# ExpandBoardZero.net
KiCad netlist of a schematic drawn in Altium Designer
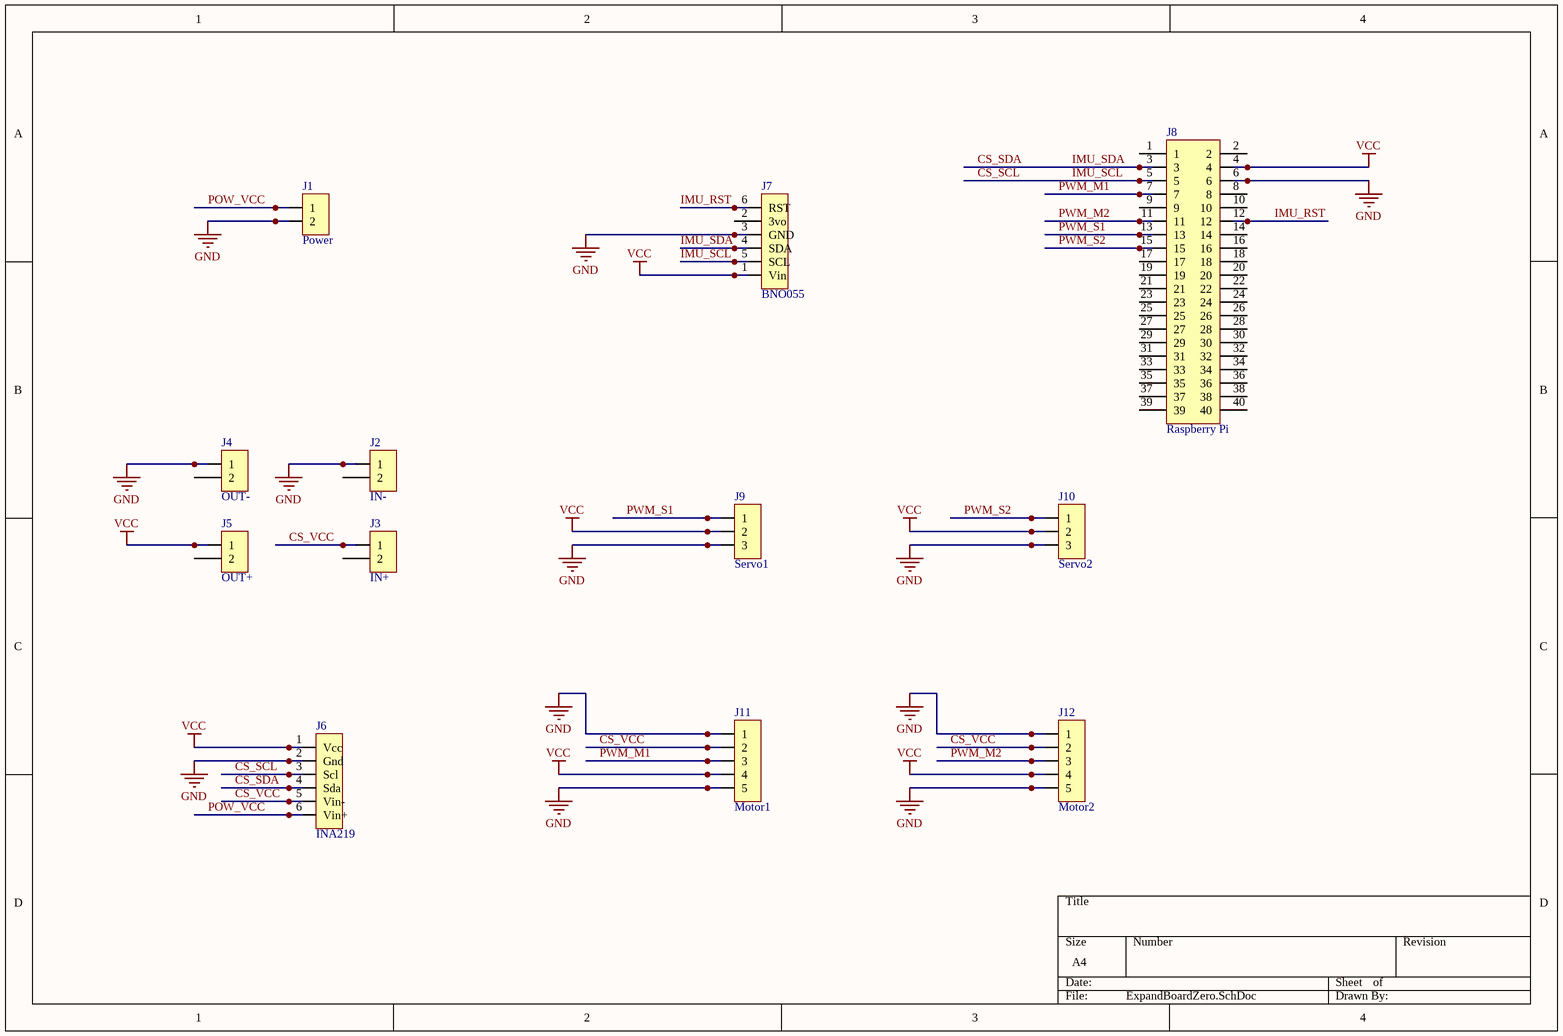
[diagram p0: ExpandBoardZero.SchDoc]

(export (version "E")
  (design (tool "Eeschema 10.0.6"))
  (components
    (comp (ref "J1")
      (value "Power")
      (footprint "Pin HDR1X2/2.54mm-S")
      (libsource (lib "排针") (part "Pin HDR1X2"))
    )
    (comp (ref "J2")
      (value "IN-")
      (footprint "Pin HDR1X2/2.54mm-S")
      (libsource (lib "排针") (part "Pin HDR1X2"))
    )
    (comp (ref "J3")
      (value "IN+")
      (footprint "Pin HDR1X2/2.54mm-S")
      (libsource (lib "排针") (part "Pin HDR1X2"))
    )
    (comp (ref "J4")
      (value "OUT-")
      (footprint "Pin HDR1X2/2.54mm-S")
      (libsource (lib "排针") (part "Pin HDR1X2"))
    )
    (comp (ref "J5")
      (value "OUT+")
      (footprint "Pin HDR1X2/2.54mm-S")
      (libsource (lib "排针") (part "Pin HDR1X2"))
    )
    (comp (ref "J6")
      (value "INA219")
      (footprint "Pin HDR1X6/2.54mm-S")
      (libsource (lib "") (part "Pin HDR1X6_1"))
    )
    (comp (ref "J7")
      (value "BNO055")
      (footprint "Pin HDR1X6/2.54mm-S")
      (libsource (lib "排针") (part "Pin HDR1X6"))
    )
    (comp (ref "J8")
      (value "Raspberry Pi")
      (footprint "Pin HDR2X20/2.54mm-S")
      (libsource (lib "排针") (part "Pin HDR2X20"))
    )
    (comp (ref "J9")
      (value "Servo1")
      (footprint "Pin HDR1X3/2.54mm-S")
      (libsource (lib "排针") (part "Pin HDR1X3"))
    )
    (comp (ref "J10")
      (value "Servo2")
      (footprint "Pin HDR1X3/2.54mm-S")
      (libsource (lib "排针") (part "Pin HDR1X3"))
    )
    (comp (ref "J11")
      (value "Motor1")
      (footprint "Pin HDR1X5/2.54mm-S")
      (libsource (lib "排针") (part "Pin HDR1X5"))
    )
    (comp (ref "J12")
      (value "Motor2")
      (footprint "Pin HDR1X5/2.54mm-S")
      (libsource (lib "排针") (part "Pin HDR1X5"))
    )
  )
  (nets
    (net (code "1") (name "/CS_SCL") (class "Default")
      (node (ref "J6") (pin "3") (pinfunction "Scl_3") (pintype "passive"))
      (node (ref "J7") (pin "5") (pinfunction "SCL_5") (pintype "passive"))
      (node (ref "J8") (pin "5") (pinfunction "5_5") (pintype "passive"))
    )
    (net (code "2") (name "/CS_SDA") (class "Default")
      (node (ref "J6") (pin "4") (pinfunction "Sda_4") (pintype "passive"))
      (node (ref "J7") (pin "4") (pinfunction "SDA_4") (pintype "passive"))
      (node (ref "J8") (pin "3") (pinfunction "3_3") (pintype "passive"))
    )
    (net (code "3") (name "/CS_VCC") (class "Default")
      (node (ref "J11") (pin "2") (pinfunction "2_2") (pintype "passive"))
      (node (ref "J12") (pin "2") (pinfunction "2_2") (pintype "passive"))
      (node (ref "J3") (pin "1") (pinfunction "1_1") (pintype "passive"))
      (node (ref "J6") (pin "5") (pinfunction "Vin-_5") (pintype "passive"))
    )
    (net (code "4") (name "/IMU_RST") (class "Default")
      (node (ref "J7") (pin "6") (pinfunction "RST_6") (pintype "passive"))
      (node (ref "J8") (pin "12") (pinfunction "12_12") (pintype "passive"))
    )
    (net (code "5") (name "/POW_VCC") (class "Default")
      (node (ref "J1") (pin "1") (pinfunction "1_1") (pintype "passive"))
      (node (ref "J6") (pin "6") (pinfunction "Vin+_6") (pintype "passive"))
    )
    (net (code "6") (name "/PWM_M1") (class "Default")
      (node (ref "J11") (pin "3") (pinfunction "3_3") (pintype "passive"))
      (node (ref "J8") (pin "7") (pinfunction "7_7") (pintype "passive"))
    )
    (net (code "7") (name "/PWM_M2") (class "Default")
      (node (ref "J12") (pin "3") (pinfunction "3_3") (pintype "passive"))
      (node (ref "J8") (pin "11") (pinfunction "11_11") (pintype "passive"))
    )
    (net (code "8") (name "/PWM_S1") (class "Default")
      (node (ref "J8") (pin "13") (pinfunction "13_13") (pintype "passive"))
      (node (ref "J9") (pin "1") (pinfunction "1_1") (pintype "passive"))
    )
    (net (code "9") (name "/PWM_S2") (class "Default")
      (node (ref "J10") (pin "1") (pinfunction "1_1") (pintype "passive"))
      (node (ref "J8") (pin "15") (pinfunction "15_15") (pintype "passive"))
    )
    (net (code "10") (name "GND") (class "Default")
      (node (ref "J1") (pin "2") (pinfunction "2_2") (pintype "passive"))
      (node (ref "J10") (pin "3") (pinfunction "3_3") (pintype "passive"))
      (node (ref "J11") (pin "1") (pinfunction "1_1") (pintype "passive"))
      (node (ref "J11") (pin "5") (pinfunction "5_5") (pintype "passive"))
      (node (ref "J12") (pin "1") (pinfunction "1_1") (pintype "passive"))
      (node (ref "J12") (pin "5") (pinfunction "5_5") (pintype "passive"))
      (node (ref "J2") (pin "1") (pinfunction "1_1") (pintype "passive"))
      (node (ref "J4") (pin "1") (pinfunction "1_1") (pintype "passive"))
      (node (ref "J6") (pin "2") (pinfunction "Gnd_2") (pintype "passive"))
      (node (ref "J7") (pin "3") (pinfunction "GND_3") (pintype "passive"))
      (node (ref "J8") (pin "6") (pinfunction "6_6") (pintype "passive"))
      (node (ref "J9") (pin "3") (pinfunction "3_3") (pintype "passive"))
    )
    (net (code "11") (name "VCC") (class "Default")
      (node (ref "J10") (pin "2") (pinfunction "2_2") (pintype "passive"))
      (node (ref "J11") (pin "4") (pinfunction "4_4") (pintype "passive"))
      (node (ref "J12") (pin "4") (pinfunction "4_4") (pintype "passive"))
      (node (ref "J5") (pin "1") (pinfunction "1_1") (pintype "passive"))
      (node (ref "J6") (pin "1") (pinfunction "Vcc_1") (pintype "passive"))
      (node (ref "J7") (pin "1") (pinfunction "Vin_1") (pintype "passive"))
      (node (ref "J8") (pin "4") (pinfunction "4_4") (pintype "passive"))
      (node (ref "J9") (pin "2") (pinfunction "2_2") (pintype "passive"))
    )
    (net (code "12") (name "unconnected-(J2-Pad2)") (class "Default")
      (node (ref "J2") (pin "2") (pinfunction "2_2") (pintype "passive"))
    )
    (net (code "13") (name "unconnected-(J3-Pad2)") (class "Default")
      (node (ref "J3") (pin "2") (pinfunction "2_2") (pintype "passive"))
    )
    (net (code "14") (name "unconnected-(J4-Pad2)") (class "Default")
      (node (ref "J4") (pin "2") (pinfunction "2_2") (pintype "passive"))
    )
    (net (code "15") (name "unconnected-(J5-Pad2)") (class "Default")
      (node (ref "J5") (pin "2") (pinfunction "2_2") (pintype "passive"))
    )
    (net (code "16") (name "unconnected-(J7-3vo-Pad2)") (class "Default")
      (node (ref "J7") (pin "2") (pinfunction "3vo_2") (pintype "passive"))
    )
    (net (code "17") (name "unconnected-(J8-Pad1)") (class "Default")
      (node (ref "J8") (pin "1") (pinfunction "1_1") (pintype "passive"))
    )
    (net (code "18") (name "unconnected-(J8-Pad2)") (class "Default")
      (node (ref "J8") (pin "2") (pinfunction "2_2") (pintype "passive"))
    )
    (net (code "19") (name "unconnected-(J8-Pad8)") (class "Default")
      (node (ref "J8") (pin "8") (pinfunction "8_8") (pintype "passive"))
    )
    (net (code "20") (name "unconnected-(J8-Pad9)") (class "Default")
      (node (ref "J8") (pin "9") (pinfunction "9_9") (pintype "passive"))
    )
    (net (code "21") (name "unconnected-(J8-Pad10)") (class "Default")
      (node (ref "J8") (pin "10") (pinfunction "10_10") (pintype "passive"))
    )
    (net (code "22") (name "unconnected-(J8-Pad14)") (class "Default")
      (node (ref "J8") (pin "14") (pinfunction "14_14") (pintype "passive"))
    )
    (net (code "23") (name "unconnected-(J8-Pad16)") (class "Default")
      (node (ref "J8") (pin "16") (pinfunction "16_16") (pintype "passive"))
    )
    (net (code "24") (name "unconnected-(J8-Pad17)") (class "Default")
      (node (ref "J8") (pin "17") (pinfunction "17_17") (pintype "passive"))
    )
    (net (code "25") (name "unconnected-(J8-Pad18)") (class "Default")
      (node (ref "J8") (pin "18") (pinfunction "18_18") (pintype "passive"))
    )
    (net (code "26") (name "unconnected-(J8-Pad19)") (class "Default")
      (node (ref "J8") (pin "19") (pinfunction "19_19") (pintype "passive"))
    )
    (net (code "27") (name "unconnected-(J8-Pad20)") (class "Default")
      (node (ref "J8") (pin "20") (pinfunction "20_20") (pintype "passive"))
    )
    (net (code "28") (name "unconnected-(J8-Pad21)") (class "Default")
      (node (ref "J8") (pin "21") (pinfunction "21_21") (pintype "passive"))
    )
    (net (code "29") (name "unconnected-(J8-Pad22)") (class "Default")
      (node (ref "J8") (pin "22") (pinfunction "22_22") (pintype "passive"))
    )
    (net (code "30") (name "unconnected-(J8-Pad23)") (class "Default")
      (node (ref "J8") (pin "23") (pinfunction "23_23") (pintype "passive"))
    )
    (net (code "31") (name "unconnected-(J8-Pad24)") (class "Default")
      (node (ref "J8") (pin "24") (pinfunction "24_24") (pintype "passive"))
    )
    (net (code "32") (name "unconnected-(J8-Pad25)") (class "Default")
      (node (ref "J8") (pin "25") (pinfunction "25_25") (pintype "passive"))
    )
    (net (code "33") (name "unconnected-(J8-Pad26)") (class "Default")
      (node (ref "J8") (pin "26") (pinfunction "26_26") (pintype "passive"))
    )
    (net (code "34") (name "unconnected-(J8-Pad27)") (class "Default")
      (node (ref "J8") (pin "27") (pinfunction "27_27") (pintype "passive"))
    )
    (net (code "35") (name "unconnected-(J8-Pad28)") (class "Default")
      (node (ref "J8") (pin "28") (pinfunction "28_28") (pintype "passive"))
    )
    (net (code "36") (name "unconnected-(J8-Pad29)") (class "Default")
      (node (ref "J8") (pin "29") (pinfunction "29_29") (pintype "passive"))
    )
    (net (code "37") (name "unconnected-(J8-Pad30)") (class "Default")
      (node (ref "J8") (pin "30") (pinfunction "30_30") (pintype "passive"))
    )
    (net (code "38") (name "unconnected-(J8-Pad31)") (class "Default")
      (node (ref "J8") (pin "31") (pinfunction "31_31") (pintype "passive"))
    )
    (net (code "39") (name "unconnected-(J8-Pad32)") (class "Default")
      (node (ref "J8") (pin "32") (pinfunction "32_32") (pintype "passive"))
    )
    (net (code "40") (name "unconnected-(J8-Pad33)") (class "Default")
      (node (ref "J8") (pin "33") (pinfunction "33_33") (pintype "passive"))
    )
    (net (code "41") (name "unconnected-(J8-Pad34)") (class "Default")
      (node (ref "J8") (pin "34") (pinfunction "34_34") (pintype "passive"))
    )
    (net (code "42") (name "unconnected-(J8-Pad35)") (class "Default")
      (node (ref "J8") (pin "35") (pinfunction "35_35") (pintype "passive"))
    )
    (net (code "43") (name "unconnected-(J8-Pad36)") (class "Default")
      (node (ref "J8") (pin "36") (pinfunction "36_36") (pintype "passive"))
    )
    (net (code "44") (name "unconnected-(J8-Pad37)") (class "Default")
      (node (ref "J8") (pin "37") (pinfunction "37_37") (pintype "passive"))
    )
    (net (code "45") (name "unconnected-(J8-Pad38)") (class "Default")
      (node (ref "J8") (pin "38") (pinfunction "38_38") (pintype "passive"))
    )
    (net (code "46") (name "unconnected-(J8-Pad39)") (class "Default")
      (node (ref "J8") (pin "39") (pinfunction "39_39") (pintype "passive"))
    )
    (net (code "47") (name "unconnected-(J8-Pad40)") (class "Default")
      (node (ref "J8") (pin "40") (pinfunction "40_40") (pintype "passive"))
    )
  )
)
